# miniwhip.net
KiCad netlist of a schematic drawn in EAGLE
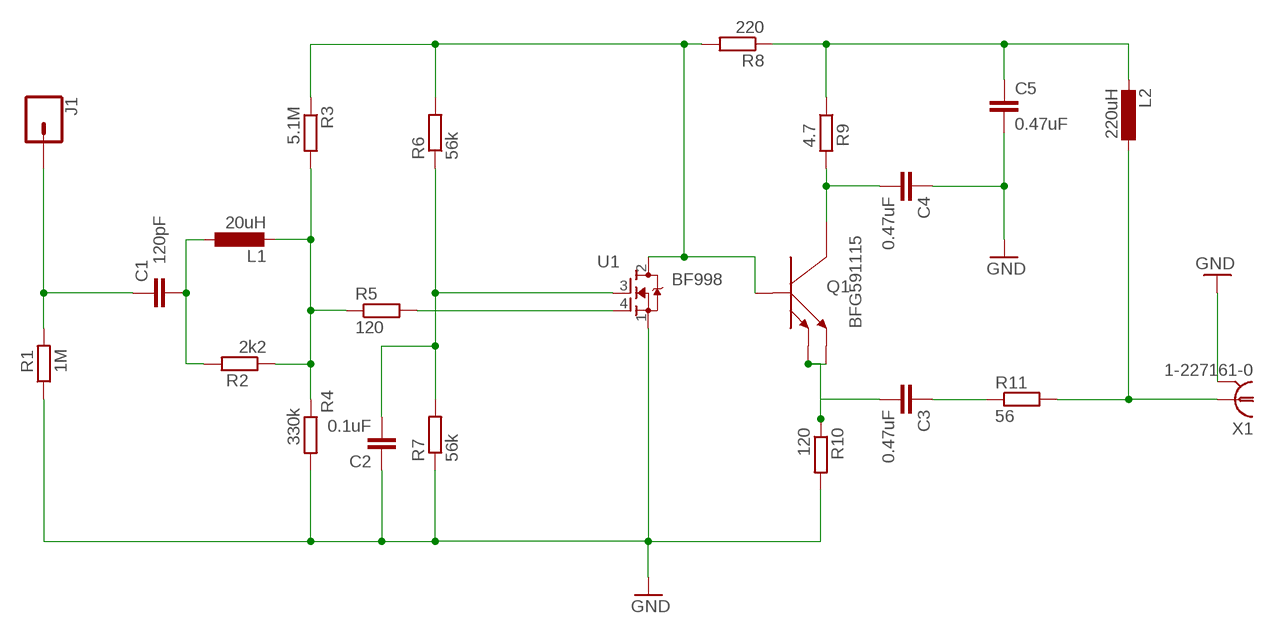
[diagram p0: schematic, sheet 1]

(export (version "E")
  (design (tool "Eeschema 10.0.6"))
  (components
    (comp (ref "C1")
      (value "120pF")
      (footprint "eagle-import:C0805")
      (libsource (lib "eagle-import") (part "C-EUC0805"))
    )
    (comp (ref "C2")
      (value "0.1uF")
      (footprint "eagle-import:C0805K")
      (libsource (lib "eagle-import") (part "C-EUC0805K"))
    )
    (comp (ref "C3")
      (value "0.47uF")
      (footprint "eagle-import:C0805K")
      (libsource (lib "eagle-import") (part "C-EUC0805K"))
    )
    (comp (ref "C4")
      (value "0.47uF")
      (footprint "eagle-import:C0805K")
      (libsource (lib "eagle-import") (part "C-EUC0805K"))
    )
    (comp (ref "C5")
      (value "0.47uF")
      (footprint "eagle-import:C0805K")
      (libsource (lib "eagle-import") (part "C-EUC0805K"))
    )
    (comp (ref "J1")
      (value "CONN_01PTH_2MM")
      (footprint "eagle-import:1X01_2MM")
      (libsource (lib "eagle-import") (part "CONN_01PTH_2MM"))
    )
    (comp (ref "L1")
      (value "20uH")
      (footprint "eagle-import:L1812")
      (libsource (lib "eagle-import") (part "L-EUL1812"))
    )
    (comp (ref "L2")
      (value "220uH")
      (footprint "eagle-import:0204_7")
      (libsource (lib "eagle-import") (part "L-EU0204/7"))
    )
    (comp (ref "Q1")
      (value "BFG591115")
      (footprint "eagle-import:SOT230P700X180-4N")
      (fields (field (name "MF") "NXP USA"))
      (libsource (lib "eagle-import") (part "BFG591115"))
    )
    (comp (ref "R1")
      (value "1M")
      (footprint "eagle-import:M0805")
      (libsource (lib "eagle-import") (part "R-EU_M0805"))
    )
    (comp (ref "R2")
      (value "2k2")
      (footprint "eagle-import:M0805")
      (libsource (lib "eagle-import") (part "R-EU_M0805"))
    )
    (comp (ref "R3")
      (value "5.1M")
      (footprint "eagle-import:0207_10")
      (libsource (lib "eagle-import") (part "R-EU_0207/10"))
    )
    (comp (ref "R4")
      (value "330k")
      (footprint "eagle-import:M0805")
      (libsource (lib "eagle-import") (part "R-EU_M0805"))
    )
    (comp (ref "R5")
      (value "120")
      (footprint "eagle-import:M0805")
      (libsource (lib "eagle-import") (part "R-EU_M0805"))
    )
    (comp (ref "R6")
      (value "56k")
      (footprint "eagle-import:M0805")
      (libsource (lib "eagle-import") (part "R-EU_M0805"))
    )
    (comp (ref "R7")
      (value "56k")
      (footprint "eagle-import:M0805")
      (libsource (lib "eagle-import") (part "R-EU_M0805"))
    )
    (comp (ref "R8")
      (value "220")
      (footprint "eagle-import:M0805")
      (libsource (lib "eagle-import") (part "R-EU_M0805"))
    )
    (comp (ref "R9")
      (value "4.7")
      (footprint "eagle-import:M0805")
      (libsource (lib "eagle-import") (part "R-EU_M0805"))
    )
    (comp (ref "R10")
      (value "120")
      (footprint "eagle-import:M0805")
      (libsource (lib "eagle-import") (part "R-EU_M0805"))
    )
    (comp (ref "R11")
      (value "56")
      (footprint "eagle-import:M0805")
      (libsource (lib "eagle-import") (part "R-EU_M0805"))
    )
    (comp (ref "U1")
      (value "BF998")
      (footprint "eagle-import:SOT190P230X110-4N")
      (fields (field (name "MF") "Infineon Technologies"))
      (libsource (lib "eagle-import") (part "BF998"))
    )
    (comp (ref "X1")
      (value "1-227161-0")
      (footprint "eagle-import:AMP_227161")
      (fields (field (name "MF") "TYCO ELECTRONICS") (field (name "MPN") "1-227161"))
      (libsource (lib "eagle-import") (part "?2271611--0"))
    )
  )
  (nets
    (net (code "1") (name "GND") (class "Default")
      (node (ref "C2") (pin "1") (pinfunction "1_1") (pintype "passive"))
      (node (ref "C4") (pin "1") (pinfunction "1_1") (pintype "passive"))
      (node (ref "C5") (pin "2") (pinfunction "2_2") (pintype "passive"))
      (node (ref "R1") (pin "1") (pinfunction "1_1") (pintype "passive"))
      (node (ref "R10") (pin "2") (pinfunction "2_2") (pintype "passive"))
      (node (ref "R4") (pin "2") (pinfunction "2_2") (pintype "passive"))
      (node (ref "R7") (pin "1") (pinfunction "1_1") (pintype "passive"))
      (node (ref "U1") (pin "1") (pinfunction "S_1") (pintype "passive"))
      (node (ref "X1") (pin "2") (pinfunction "2_2") (pintype "passive"))
    )
    (net (code "2") (name "Net-(C1-Pad1)") (class "Default")
      (node (ref "C1") (pin "1") (pinfunction "1_1") (pintype "passive"))
      (node (ref "J1") (pin "1") (pinfunction "1_1") (pintype "passive"))
      (node (ref "R1") (pin "2") (pinfunction "2_2") (pintype "passive"))
    )
    (net (code "3") (name "Net-(C1-Pad2)") (class "Default")
      (node (ref "C1") (pin "2") (pinfunction "2_2") (pintype "passive"))
      (node (ref "L1") (pin "1") (pinfunction "1_1") (pintype "passive"))
      (node (ref "R2") (pin "2") (pinfunction "2_2") (pintype "passive"))
    )
    (net (code "4") (name "Net-(C3-Pad1)") (class "Default")
      (node (ref "C3") (pin "1") (pinfunction "1_1") (pintype "passive"))
      (node (ref "R11") (pin "1") (pinfunction "1_1") (pintype "passive"))
    )
    (net (code "5") (name "Net-(C5-Pad1)") (class "Default")
      (node (ref "C5") (pin "1") (pinfunction "1_1") (pintype "passive"))
      (node (ref "L2") (pin "2") (pinfunction "2_2") (pintype "passive"))
      (node (ref "R8") (pin "1") (pinfunction "1_1") (pintype "passive"))
      (node (ref "R9") (pin "1") (pinfunction "1_1") (pintype "passive"))
    )
    (net (code "6") (name "Net-(L1-Pad2)") (class "Default")
      (node (ref "L1") (pin "2") (pinfunction "2_2") (pintype "passive"))
      (node (ref "R2") (pin "1") (pinfunction "1_1") (pintype "passive"))
      (node (ref "R3") (pin "2") (pinfunction "2_2") (pintype "passive"))
      (node (ref "R4") (pin "1") (pinfunction "1_1") (pintype "passive"))
      (node (ref "R5") (pin "1") (pinfunction "1_1") (pintype "passive"))
    )
    (net (code "7") (name "Net-(L2-Pad1)") (class "Default")
      (node (ref "L2") (pin "1") (pinfunction "1_1") (pintype "passive"))
      (node (ref "R11") (pin "2") (pinfunction "2_2") (pintype "passive"))
      (node (ref "X1") (pin "1") (pinfunction "1_1") (pintype "passive"))
    )
    (net (code "8") (name "Net-(Q1-B)") (class "Default")
      (node (ref "Q1") (pin "2") (pinfunction "B_2") (pintype "passive"))
      (node (ref "R3") (pin "1") (pinfunction "1_1") (pintype "passive"))
      (node (ref "R6") (pin "2") (pinfunction "2_2") (pintype "passive"))
      (node (ref "R8") (pin "2") (pinfunction "2_2") (pintype "passive"))
      (node (ref "U1") (pin "2") (pinfunction "D_2") (pintype "passive"))
    )
    (net (code "9") (name "Net-(Q1-C)") (class "Default")
      (node (ref "C4") (pin "2") (pinfunction "2_2") (pintype "passive"))
      (node (ref "Q1") (pin "4") (pinfunction "C_4") (pintype "passive"))
      (node (ref "R9") (pin "2") (pinfunction "2_2") (pintype "passive"))
    )
    (net (code "10") (name "Net-(Q1-E1)") (class "Default")
      (node (ref "C3") (pin "2") (pinfunction "2_2") (pintype "passive"))
      (node (ref "Q1") (pin "1") (pinfunction "E1_1") (pintype "passive"))
      (node (ref "Q1") (pin "3") (pinfunction "E2_3") (pintype "passive"))
      (node (ref "R10") (pin "1") (pinfunction "1_1") (pintype "passive"))
    )
    (net (code "11") (name "Net-(U1-G)") (class "Default")
      (node (ref "C2") (pin "2") (pinfunction "2_2") (pintype "passive"))
      (node (ref "R6") (pin "1") (pinfunction "1_1") (pintype "passive"))
      (node (ref "R7") (pin "2") (pinfunction "2_2") (pintype "passive"))
      (node (ref "U1") (pin "3") (pinfunction "G_3") (pintype "passive"))
    )
    (net (code "12") (name "Net-(U1-G1)") (class "Default")
      (node (ref "R5") (pin "2") (pinfunction "2_2") (pintype "passive"))
      (node (ref "U1") (pin "4") (pinfunction "G1_4") (pintype "passive"))
    )
  )
)
